# Sheet1.net
KiCad netlist of a schematic drawn in Altium Designer
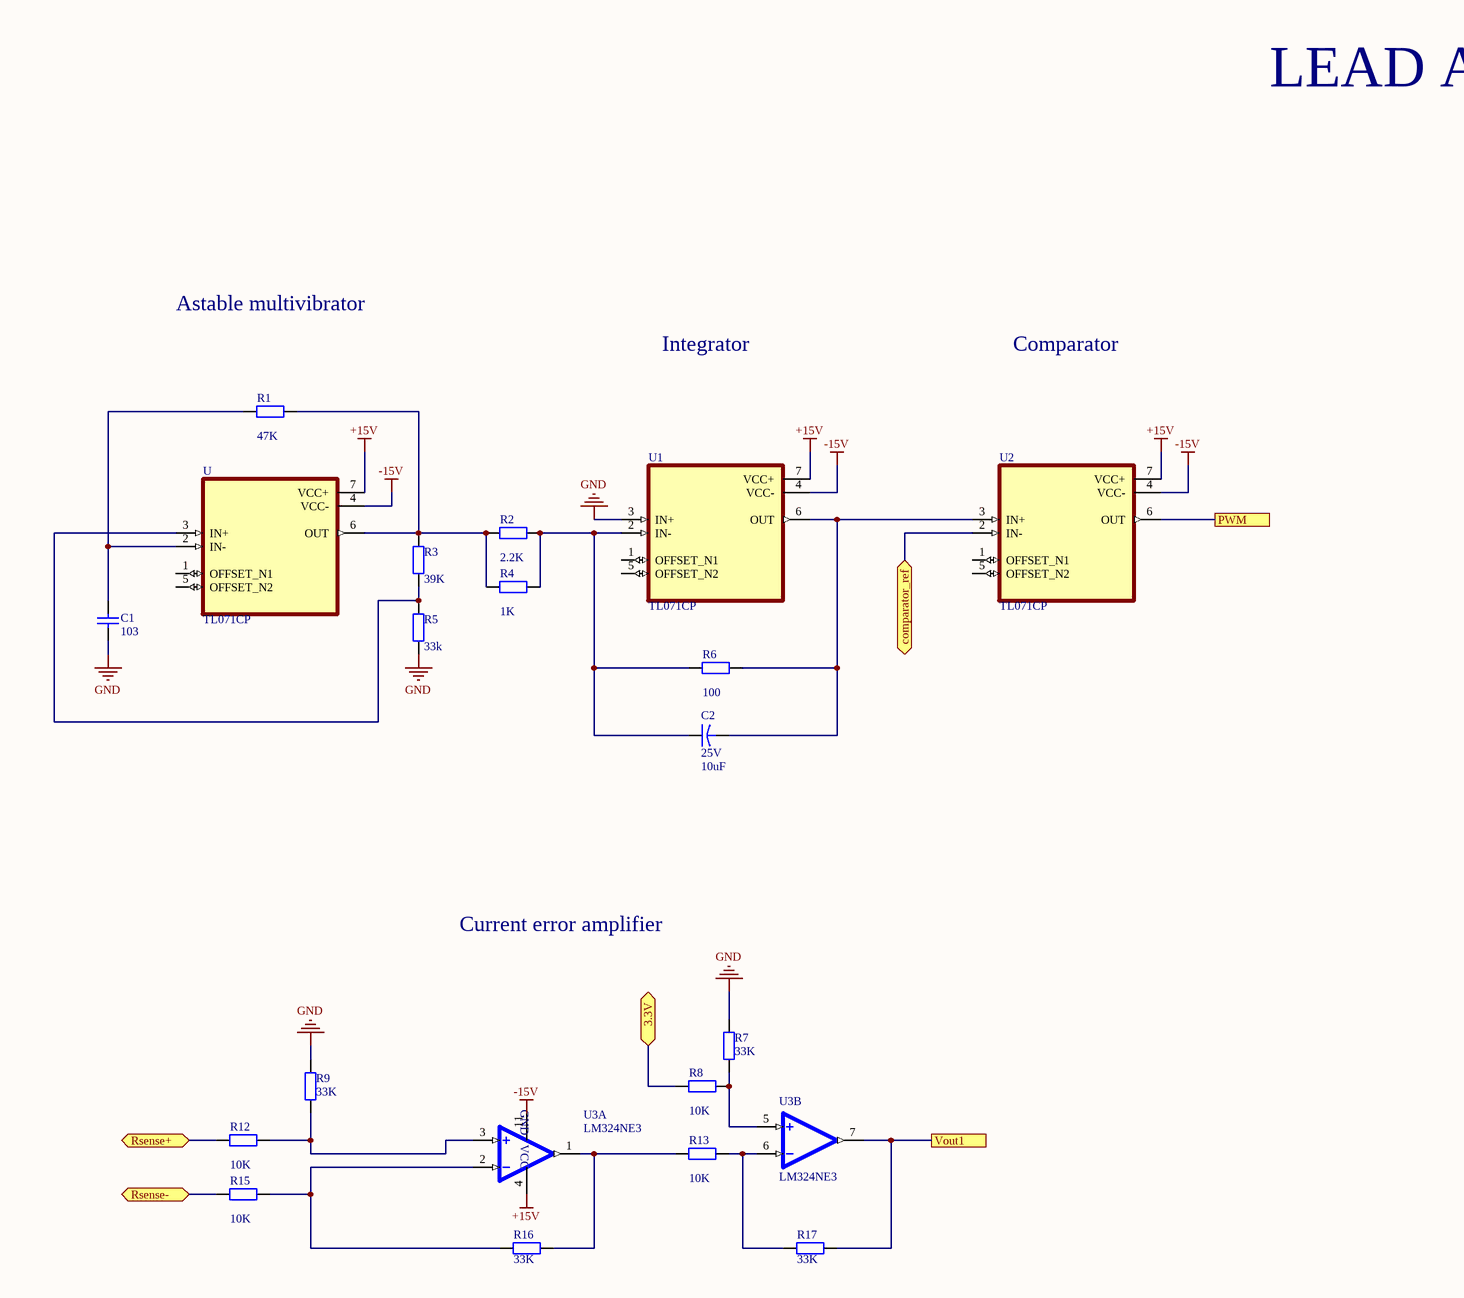
[diagram p0: Sheet1.SchDoc, top left]
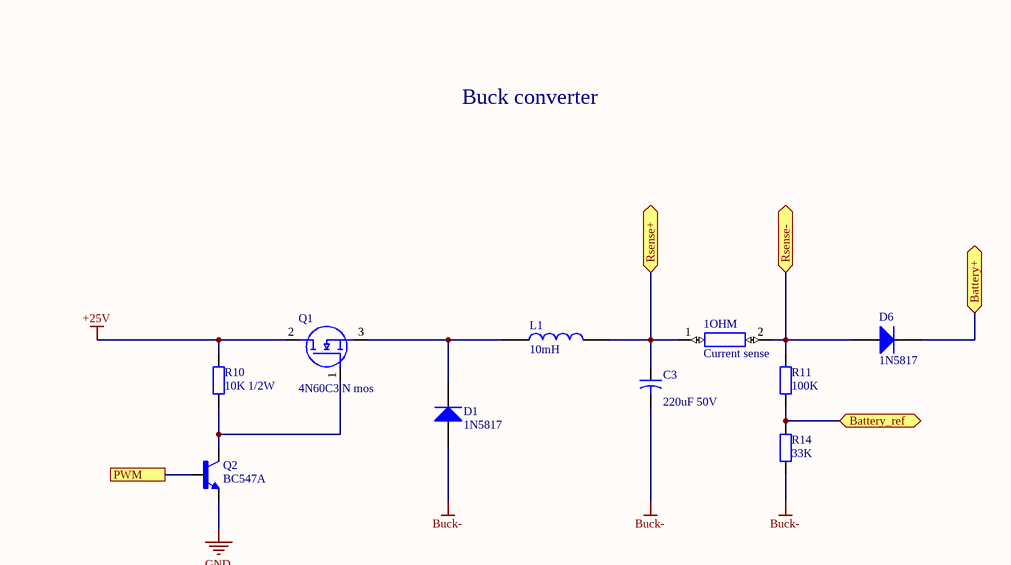
[diagram p1: Sheet1.SchDoc, top right]
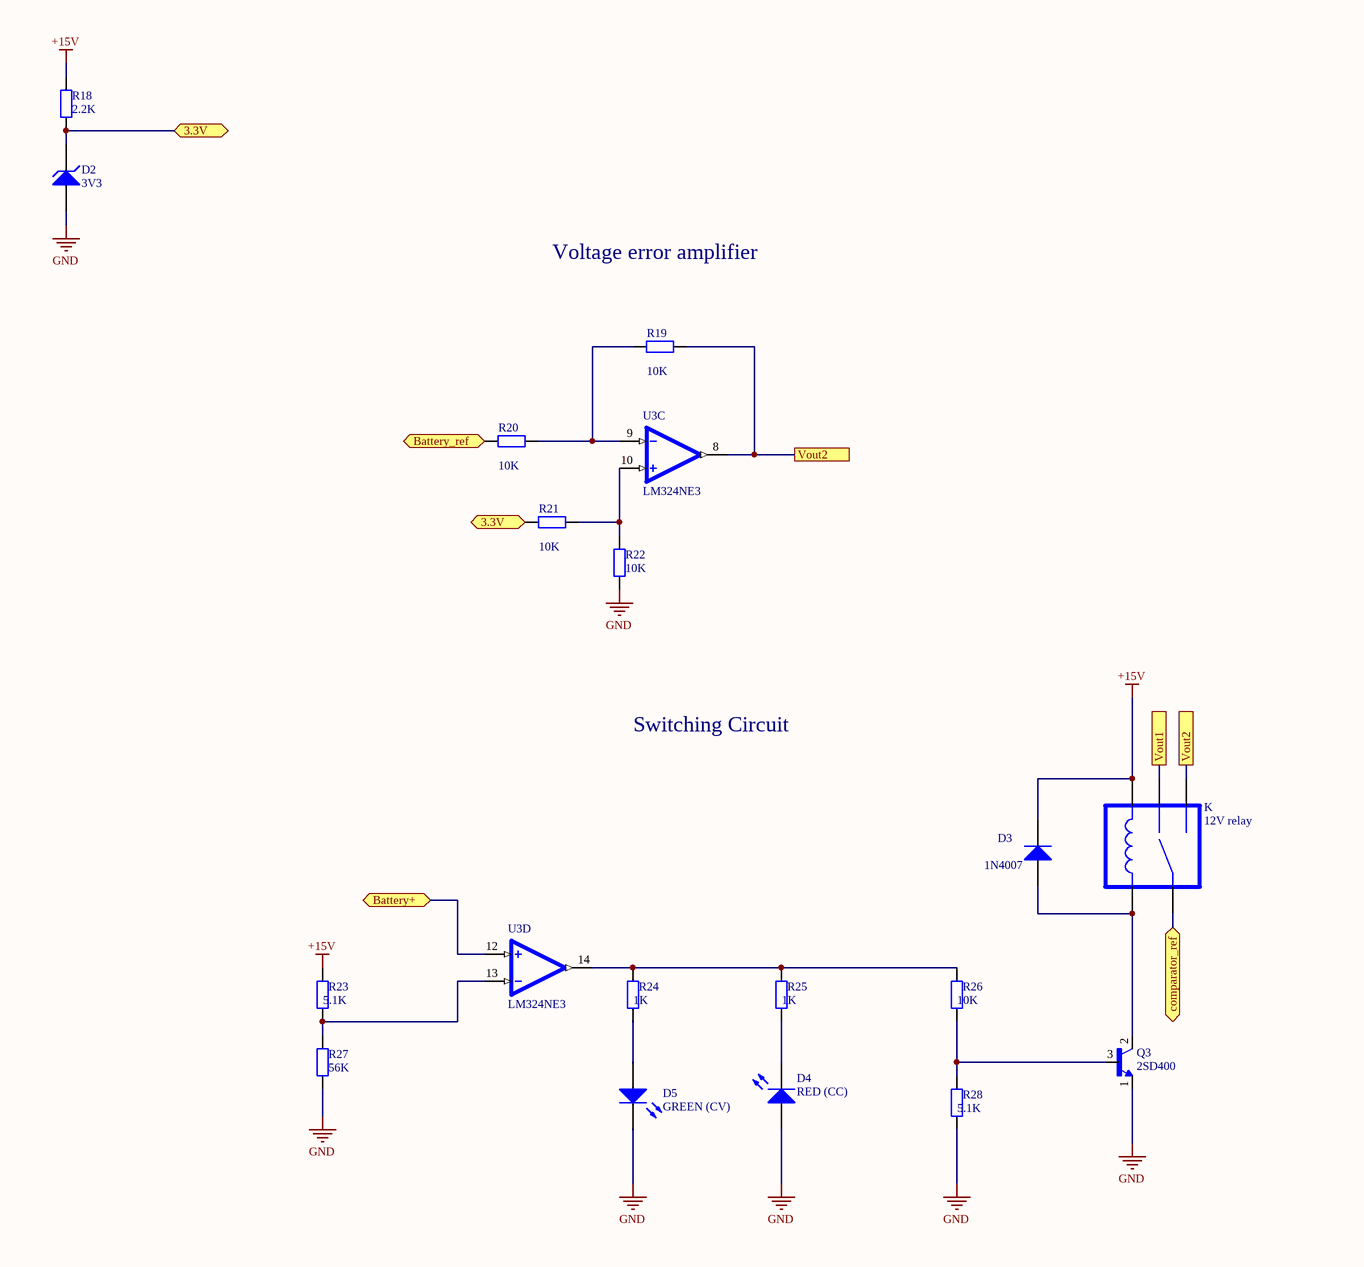
[diagram p2: Sheet1.SchDoc, bottom left]

(export (version "E")
  (design (tool "Eeschema 10.0.6"))
  (components
    (comp (ref "1OHM")
      (value "Current sense")
      (footprint "RESAD5860W102L2380D870")
      (description "25 kOhms Â±1% 5W Through Hole Resistor Axial Wirewound")
      (fields (field (name "MF") "Ohmite") (field (name "MP") "45F25KE"))
      (libsource (lib "45F25KE") (part "45F25KE"))
    )
    (comp (ref "C1")
      (value "103")
      (footprint "RAD-0.3")
      (description "Capacitor")
      (fields (field (name "PUBLISHER") "Altium Limited"))
      (libsource (lib "Miscellaneous Devices") (part "Cap"))
    )
    (comp (ref "C2")
      (value "25V")
      (footprint "CAPR5-4X5")
      (description "Capacitor")
      (fields (field (name "ALTIUM_VALUE") "10uF") (field (name "PUBLISHER") "Altium Limited"))
      (libsource (lib "Miscellaneous Devices") (part "Cap2"))
    )
    (comp (ref "C3")
      (value "220uF 50V")
      (footprint "CAPR5-4X5")
      (description "Capacitor")
      (fields (field (name "Comment") "Cap2") (field (name "PUBLISHER") "Altium Limited"))
      (libsource (lib "Miscellaneous Devices") (part "Cap2"))
    )
    (comp (ref "D1")
      (value "1N5817")
      (footprint "DO-41")
      (description "1 Amp General Purpose Rectifier")
      (fields (field (name "PUBLISHER") "Altium Limited"))
      (libsource (lib "Miscellaneous Devices") (part "Diode 1N4007"))
    )
    (comp (ref "D2")
      (value "3V3")
      (footprint "DIODE-0.7")
      (description "Zener Diode")
      (fields (field (name "PUBLISHER") "Altium Limited"))
      (libsource (lib "Miscellaneous Devices") (part "D Zener"))
    )
    (comp (ref "D3")
      (value "1N4007")
      (footprint "DO-41")
      (description "1 Amp General Purpose Rectifier")
      (fields (field (name "PUBLISHER") "Altium Limited"))
      (libsource (lib "Miscellaneous Devices") (part "Diode 1N4007"))
    )
    (comp (ref "D4")
      (value "RED (CC)")
      (footprint "LED-1")
      (description "Typical RED GaAs LED")
      (fields (field (name "PUBLISHER") "Altium Limited"))
      (libsource (lib "Miscellaneous Devices") (part "LED1"))
    )
    (comp (ref "D5")
      (value "GREEN (CV)")
      (footprint "LED-1")
      (description "Typical RED GaAs LED")
      (fields (field (name "PUBLISHER") "Altium Limited"))
      (libsource (lib "Miscellaneous Devices") (part "LED1"))
    )
    (comp (ref "D6")
      (value "1N5817")
      (footprint "DO-41")
      (description "1 Amp General Purpose Rectifier")
      (fields (field (name "PUBLISHER") "Altium Limited"))
      (libsource (lib "Miscellaneous Devices") (part "Diode 1N4007"))
    )
    (comp (ref "K")
      (value "12V relay")
      (footprint "TE_1461069-5")
      (description "General Purpose Relay SPDT _1 Form C_ 12VDC Coil Through Hole")
      (fields (field (name "MP") "1461069-5") (field (name "MF") "TE Connectivity"))
      (libsource (lib "1461069-5") (part "1461069-5"))
    )
    (comp (ref "L1")
      (value "10mH")
      (footprint "PE92102KNL")
      (description "Pulse 100 uH +/-20% Leaded Inductor, 2.6A Idc, 100m Rdc")
      (fields
        (field (name "MANUFACTURER_PART_NUMBER") "PE-92102KNL")
        (field (name "MOUSER PART NUMBER") "673-PE-92102KNL")
      )
      (libsource (lib "PE-92102KNL") (part "PE-92102KNL"))
    )
    (comp (ref "Q1")
      (value "4N60C3 N mos")
      (footprint "TO544P516X1586X2557-3P")
      (description "Infineon SPW24N60C3 N-channel MOSFET Transistor, 24.3 A, 650 V, 3-Pin TO-247")
      (fields
        (field (name "MANUFACTURER_PART_NUMBER") "SPW24N60C3")
        (field (name "MOUSER PART NUMBER") "726-SPW24N60C3")
      )
      (libsource (lib "SPW24N60C3") (part "SPW24N60C3"))
    )
    (comp (ref "Q2")
      (value "BC547A")
      (footprint "TO92250P510H770-3")
      (description "Bipolar (BJT) Transistor NPN 45 V 100 mA 300MHz 625 mW Through Hole TO-92 (TO-226)")
      (fields (field (name "MF") "ON Semiconductor"))
      (libsource (lib "BC547A") (part "BC547A"))
    )
    (comp (ref "Q3")
      (value "2SD400")
      (footprint "TO92250P510H770-3:TO92250P510H770-3")
      (description "TO-92MOD Transistor (NPN). Low-Frequency Power Amp, Electronic Governor Applications.")
      (fields (field (name "MF") "LGE"))
      (libsource (lib "2SD400") (part "2SD400"))
    )
    (comp (ref "R1")
      (value "47K")
      (footprint "AXIAL-0.4")
      (description "Resistor")
      (fields (field (name "Comment") "Res2") (field (name "PUBLISHER") "Altium Limited"))
      (libsource (lib "") (part "Res2_1"))
    )
    (comp (ref "R2")
      (value "2.2K")
      (footprint "AXIAL-0.4")
      (description "Resistor")
      (fields (field (name "Comment") "Res2") (field (name "PUBLISHER") "Altium Limited"))
      (libsource (lib "") (part "Res2_1"))
    )
    (comp (ref "R3")
      (value "39K")
      (footprint "AXIAL-0.4")
      (description "Resistor")
      (fields (field (name "Comment") "Res2") (field (name "PUBLISHER") "Altium Limited"))
      (libsource (lib "") (part "Res2_2"))
    )
    (comp (ref "R4")
      (value "1K")
      (footprint "AXIAL-0.4")
      (description "Resistor")
      (fields (field (name "Comment") "Res2") (field (name "PUBLISHER") "Altium Limited"))
      (libsource (lib "") (part "Res2_1"))
    )
    (comp (ref "R5")
      (value "33k")
      (footprint "AXIAL-0.4")
      (description "Resistor")
      (fields (field (name "Comment") "Res2") (field (name "PUBLISHER") "Altium Limited"))
      (libsource (lib "") (part "Res2_2"))
    )
    (comp (ref "R6")
      (value "100")
      (footprint "AXIAL-0.4")
      (description "Resistor")
      (fields (field (name "Comment") "Res2") (field (name "PUBLISHER") "Altium Limited"))
      (libsource (lib "") (part "Res2_1"))
    )
    (comp (ref "R7")
      (value "33K")
      (footprint "AXIAL-0.4")
      (description "Resistor")
      (fields (field (name "Comment") "Res2") (field (name "PUBLISHER") "Altium Limited"))
      (libsource (lib "Miscellaneous Devices") (part "Res2"))
    )
    (comp (ref "R8")
      (value "10K")
      (footprint "AXIAL-0.4")
      (description "Resistor")
      (fields (field (name "Comment") "Res2") (field (name "PUBLISHER") "Altium Limited"))
      (libsource (lib "") (part "Res2_1"))
    )
    (comp (ref "R9")
      (value "33K")
      (footprint "AXIAL-0.4")
      (description "Resistor")
      (fields (field (name "Comment") "Res2") (field (name "PUBLISHER") "Altium Limited"))
      (libsource (lib "") (part "Res2_2"))
    )
    (comp (ref "R10")
      (value "10K 1/2W")
      (footprint "AXIAL-0.4")
      (description "Resistor")
      (fields (field (name "Comment") "Res2") (field (name "PUBLISHER") "Altium Limited"))
      (libsource (lib "Miscellaneous Devices") (part "Res2"))
    )
    (comp (ref "R11")
      (value "100K")
      (footprint "AXIAL-0.4")
      (description "Resistor")
      (fields (field (name "Comment") "Res2") (field (name "PUBLISHER") "Altium Limited"))
      (libsource (lib "Miscellaneous Devices") (part "Res2"))
    )
    (comp (ref "R12")
      (value "10K")
      (footprint "AXIAL-0.4")
      (description "Resistor")
      (fields (field (name "Comment") "Res2") (field (name "PUBLISHER") "Altium Limited"))
      (libsource (lib "") (part "Res2_1"))
    )
    (comp (ref "R13")
      (value "10K")
      (footprint "AXIAL-0.4")
      (description "Resistor")
      (fields (field (name "Comment") "Res2") (field (name "PUBLISHER") "Altium Limited"))
      (libsource (lib "") (part "Res2_1"))
    )
    (comp (ref "R14")
      (value "33K")
      (footprint "AXIAL-0.4")
      (description "Resistor")
      (fields (field (name "Comment") "Res2") (field (name "PUBLISHER") "Altium Limited"))
      (libsource (lib "Miscellaneous Devices") (part "Res2"))
    )
    (comp (ref "R15")
      (value "10K")
      (footprint "AXIAL-0.4")
      (description "Resistor")
      (fields (field (name "Comment") "Res2") (field (name "PUBLISHER") "Altium Limited"))
      (libsource (lib "") (part "Res2_1"))
    )
    (comp (ref "R16")
      (value "33K")
      (footprint "AXIAL-0.4")
      (description "Resistor")
      (fields (field (name "Comment") "Res2") (field (name "PUBLISHER") "Altium Limited"))
      (libsource (lib "") (part "Res2_3"))
    )
    (comp (ref "R17")
      (value "33K")
      (footprint "AXIAL-0.4")
      (description "Resistor")
      (fields (field (name "Comment") "Res2") (field (name "PUBLISHER") "Altium Limited"))
      (libsource (lib "") (part "Res2_3"))
    )
    (comp (ref "R18")
      (value "2.2K")
      (footprint "AXIAL-0.4")
      (description "Resistor")
      (fields (field (name "Comment") "Res2") (field (name "PUBLISHER") "Altium Limited"))
      (libsource (lib "") (part "Res2_2"))
    )
    (comp (ref "R19")
      (value "10K")
      (footprint "AXIAL-0.4")
      (description "Resistor")
      (fields (field (name "Comment") "Res2") (field (name "PUBLISHER") "Altium Limited"))
      (libsource (lib "") (part "Res2_1"))
    )
    (comp (ref "R20")
      (value "10K")
      (footprint "AXIAL-0.4")
      (description "Resistor")
      (fields (field (name "Comment") "Res2") (field (name "PUBLISHER") "Altium Limited"))
      (libsource (lib "") (part "Res2_1"))
    )
    (comp (ref "R21")
      (value "10K")
      (footprint "AXIAL-0.4")
      (description "Resistor")
      (fields (field (name "Comment") "Res2") (field (name "PUBLISHER") "Altium Limited"))
      (libsource (lib "") (part "Res2_1"))
    )
    (comp (ref "R22")
      (value "10K")
      (footprint "AXIAL-0.4")
      (description "Resistor")
      (fields (field (name "Comment") "Res2") (field (name "PUBLISHER") "Altium Limited"))
      (libsource (lib "") (part "Res2_2"))
    )
    (comp (ref "R23")
      (value "5.1K")
      (footprint "AXIAL-0.4")
      (description "Resistor")
      (fields (field (name "Comment") "Res2") (field (name "PUBLISHER") "Altium Limited"))
      (libsource (lib "") (part "Res2_2"))
    )
    (comp (ref "R24")
      (value "1K")
      (footprint "AXIAL-0.4")
      (description "Resistor")
      (fields (field (name "Comment") "Res2") (field (name "PUBLISHER") "Altium Limited"))
      (libsource (lib "") (part "Res2_2"))
    )
    (comp (ref "R25")
      (value "1K")
      (footprint "AXIAL-0.4")
      (description "Resistor")
      (fields (field (name "Comment") "Res2") (field (name "PUBLISHER") "Altium Limited"))
      (libsource (lib "") (part "Res2_2"))
    )
    (comp (ref "R26")
      (value "10K")
      (footprint "AXIAL-0.4")
      (description "Resistor")
      (fields (field (name "Comment") "Res2") (field (name "PUBLISHER") "Altium Limited"))
      (libsource (lib "") (part "Res2_2"))
    )
    (comp (ref "R27")
      (value "56K")
      (footprint "AXIAL-0.4")
      (description "Resistor")
      (fields (field (name "Comment") "Res2") (field (name "PUBLISHER") "Altium Limited"))
      (libsource (lib "") (part "Res2_2"))
    )
    (comp (ref "R28")
      (value "5.1K")
      (footprint "AXIAL-0.4")
      (description "Resistor")
      (fields (field (name "Comment") "Res2") (field (name "PUBLISHER") "Altium Limited"))
      (libsource (lib "") (part "Res2_2"))
    )
    (comp (ref "U")
      (value "TL071CP")
      (footprint "DIP794W45P254L959H508Q8")
      (description "Low-Noise JFET-Input General-Purpose Operational Amplifier 8-PDIP 0 to 70")
      (fields (field (name "MF") "Texas Instruments"))
      (libsource (lib "TL071CP") (part "TL071CP"))
    )
    (comp (ref "U1")
      (value "TL071CP")
      (footprint "DIP794W45P254L959H508Q8")
      (description "Low-Noise JFET-Input General-Purpose Operational Amplifier 8-PDIP 0 to 70")
      (fields (field (name "MF") "Texas Instruments"))
      (libsource (lib "TL071CP") (part "TL071CP"))
    )
    (comp (ref "U2")
      (value "TL071CP")
      (footprint "DIP794W45P254L959H508Q8")
      (description "Low-Noise JFET-Input General-Purpose Operational Amplifier 8-PDIP 0 to 70")
      (fields (field (name "MF") "Texas Instruments"))
      (libsource (lib "TL071CP") (part "TL071CP"))
    )
    (comp (ref "U3")
      (value "LM324NE3")
      (footprint "DIP794W45P254L1969H508Q14")
      (description "Quad, 30-V, 1.2-MHz operational amplifier")
      (fields (field (name "MF") "Texas Instruments"))
      (libsource (lib "LM324NE3") (part "LM324NE3"))
    )
  )
  (nets
    (net (code "1") (name "+15V") (class "Default")
      (node (ref "D3") (pin "2") (pinfunction "K_2") (pintype "passive"))
      (node (ref "K") (pin "5") (pinfunction "M2_5") (pintype "passive"))
      (node (ref "R18") (pin "2") (pinfunction "2_2") (pintype "passive"))
      (node (ref "R23") (pin "2") (pinfunction "2_2") (pintype "passive"))
      (node (ref "U") (pin "7") (pinfunction "VCC+_7") (pintype "power_in"))
      (node (ref "U1") (pin "7") (pinfunction "VCC+_7") (pintype "power_in"))
      (node (ref "U2") (pin "7") (pinfunction "VCC+_7") (pintype "power_in"))
      (node (ref "U3") (pin "4") (pinfunction "VCC_4") (pintype "power_in"))
    )
    (net (code "2") (name "+25V") (class "Default")
      (node (ref "Q1") (pin "2") (pinfunction "D_2") (pintype "passive"))
      (node (ref "R10") (pin "1") (pinfunction "1_1") (pintype "passive"))
    )
    (net (code "3") (name "-15V") (class "Default")
      (node (ref "U") (pin "4") (pinfunction "VCC-_4") (pintype "power_in"))
      (node (ref "U1") (pin "4") (pinfunction "VCC-_4") (pintype "power_in"))
      (node (ref "U2") (pin "4") (pinfunction "VCC-_4") (pintype "power_in"))
      (node (ref "U3") (pin "11") (pinfunction "GND_11") (pintype "power_in"))
    )
    (net (code "4") (name "/3.3V") (class "Default")
      (node (ref "D2") (pin "2") (pinfunction "K_2") (pintype "passive"))
      (node (ref "R18") (pin "1") (pinfunction "1_1") (pintype "passive"))
      (node (ref "R21") (pin "1") (pinfunction "1_1") (pintype "passive"))
      (node (ref "R8") (pin "1") (pinfunction "1_1") (pintype "passive"))
    )
    (net (code "5") (name "/Battery+") (class "Default")
      (node (ref "D6") (pin "2") (pinfunction "K_2") (pintype "passive"))
      (node (ref "U3") (pin "12") (pinfunction "4IN+_12") (pintype "input"))
    )
    (net (code "6") (name "/Battery_ref") (class "Default")
      (node (ref "R11") (pin "2") (pinfunction "2_2") (pintype "passive"))
      (node (ref "R14") (pin "1") (pinfunction "1_1") (pintype "passive"))
      (node (ref "R20") (pin "1") (pinfunction "1_1") (pintype "passive"))
    )
    (net (code "7") (name "/PWM") (class "Default")
      (node (ref "Q2") (pin "2") (pinfunction "B_2") (pintype "passive"))
      (node (ref "U2") (pin "6") (pinfunction "OUT_6") (pintype "output"))
    )
    (net (code "8") (name "/Rsense+") (class "Default")
      (node (ref "1OHM") (pin "1") (pinfunction "1_1") (pintype "bidirectional"))
      (node (ref "C3") (pin "1") (pinfunction "1_1") (pintype "passive"))
      (node (ref "L1") (pin "2") (pinfunction "2_2") (pintype "passive"))
      (node (ref "R12") (pin "1") (pinfunction "1_1") (pintype "passive"))
    )
    (net (code "9") (name "/Rsense-") (class "Default")
      (node (ref "1OHM") (pin "2") (pinfunction "2_2") (pintype "bidirectional"))
      (node (ref "D6") (pin "1") (pinfunction "A_1") (pintype "passive"))
      (node (ref "R11") (pin "1") (pinfunction "1_1") (pintype "passive"))
      (node (ref "R15") (pin "1") (pinfunction "1_1") (pintype "passive"))
    )
    (net (code "10") (name "/Vout1") (class "Default")
      (node (ref "K") (pin "4") (pinfunction "NC_4") (pintype "passive"))
      (node (ref "R17") (pin "1") (pinfunction "1_1") (pintype "passive"))
      (node (ref "U3") (pin "7") (pinfunction "2OUT_7") (pintype "output"))
    )
    (net (code "11") (name "/Vout2") (class "Default")
      (node (ref "K") (pin "3") (pinfunction "NO_3") (pintype "passive"))
      (node (ref "R19") (pin "2") (pinfunction "2_2") (pintype "passive"))
      (node (ref "U3") (pin "8") (pinfunction "3OUT_8") (pintype "output"))
    )
    (net (code "12") (name "/comparator_ref") (class "Default")
      (node (ref "K") (pin "1") (pinfunction "C_1") (pintype "passive"))
      (node (ref "U2") (pin "2") (pinfunction "IN-_2") (pintype "input"))
    )
    (net (code "13") (name "Buck-") (class "Default")
      (node (ref "C3") (pin "2") (pinfunction "2_2") (pintype "passive"))
      (node (ref "D1") (pin "1") (pinfunction "A_1") (pintype "passive"))
      (node (ref "R14") (pin "2") (pinfunction "2_2") (pintype "passive"))
    )
    (net (code "14") (name "GND") (class "Default")
      (node (ref "C1") (pin "1") (pinfunction "1_1") (pintype "passive"))
      (node (ref "D2") (pin "1") (pinfunction "A_1") (pintype "passive"))
      (node (ref "D4") (pin "1") (pinfunction "A_1") (pintype "passive"))
      (node (ref "D5") (pin "2") (pinfunction "K_2") (pintype "passive"))
      (node (ref "Q2") (pin "3") (pinfunction "E_3") (pintype "passive"))
      (node (ref "Q3") (pin "1") (pinfunction "E_1") (pintype "passive"))
      (node (ref "R22") (pin "1") (pinfunction "1_1") (pintype "passive"))
      (node (ref "R27") (pin "1") (pinfunction "1_1") (pintype "passive"))
      (node (ref "R28") (pin "1") (pinfunction "1_1") (pintype "passive"))
      (node (ref "R5") (pin "1") (pinfunction "1_1") (pintype "passive"))
      (node (ref "R7") (pin "1") (pinfunction "1_1") (pintype "passive"))
      (node (ref "R9") (pin "2") (pinfunction "2_2") (pintype "passive"))
      (node (ref "U1") (pin "3") (pinfunction "IN+_3") (pintype "input"))
    )
    (net (code "15") (name "Net-(D1-K)") (class "Default")
      (node (ref "D1") (pin "2") (pinfunction "K_2") (pintype "passive"))
      (node (ref "L1") (pin "1") (pinfunction "1_1") (pintype "passive"))
      (node (ref "Q1") (pin "3") (pinfunction "S_3") (pintype "passive"))
    )
    (net (code "16") (name "Net-(D3-A)") (class "Default")
      (node (ref "D3") (pin "1") (pinfunction "A_1") (pintype "passive"))
      (node (ref "K") (pin "2") (pinfunction "M1_2") (pintype "passive"))
      (node (ref "Q3") (pin "2") (pinfunction "C_2") (pintype "passive"))
    )
    (net (code "17") (name "Net-(D4-K)") (class "Default")
      (node (ref "D4") (pin "2") (pinfunction "K_2") (pintype "passive"))
      (node (ref "R25") (pin "1") (pinfunction "1_1") (pintype "passive"))
    )
    (net (code "18") (name "Net-(D5-A)") (class "Default")
      (node (ref "D5") (pin "1") (pinfunction "A_1") (pintype "passive"))
      (node (ref "R24") (pin "1") (pinfunction "1_1") (pintype "passive"))
    )
    (net (code "19") (name "Net-(Q1-G)") (class "Default")
      (node (ref "Q1") (pin "1") (pinfunction "G_1") (pintype "passive"))
      (node (ref "Q2") (pin "1") (pinfunction "C_1") (pintype "passive"))
      (node (ref "R10") (pin "2") (pinfunction "2_2") (pintype "passive"))
    )
    (net (code "20") (name "Net-(Q3-B)") (class "Default")
      (node (ref "Q3") (pin "3") (pinfunction "B_3") (pintype "passive"))
      (node (ref "R26") (pin "1") (pinfunction "1_1") (pintype "passive"))
      (node (ref "R28") (pin "2") (pinfunction "2_2") (pintype "passive"))
    )
    (net (code "21") (name "Net-(U-IN+)") (class "Default")
      (node (ref "R3") (pin "1") (pinfunction "1_1") (pintype "passive"))
      (node (ref "R5") (pin "2") (pinfunction "2_2") (pintype "passive"))
      (node (ref "U") (pin "3") (pinfunction "IN+_3") (pintype "input"))
    )
    (net (code "22") (name "Net-(U-IN-)") (class "Default")
      (node (ref "C1") (pin "2") (pinfunction "2_2") (pintype "passive"))
      (node (ref "R1") (pin "1") (pinfunction "1_1") (pintype "passive"))
      (node (ref "U") (pin "2") (pinfunction "IN-_2") (pintype "input"))
    )
    (net (code "23") (name "Net-(U-OUT)") (class "Default")
      (node (ref "R1") (pin "2") (pinfunction "2_2") (pintype "passive"))
      (node (ref "R2") (pin "1") (pinfunction "1_1") (pintype "passive"))
      (node (ref "R3") (pin "2") (pinfunction "2_2") (pintype "passive"))
      (node (ref "R4") (pin "1") (pinfunction "1_1") (pintype "passive"))
      (node (ref "U") (pin "6") (pinfunction "OUT_6") (pintype "output"))
    )
    (net (code "24") (name "Net-(U1-IN-)") (class "Default")
      (node (ref "C2") (pin "1") (pinfunction "1_1") (pintype "passive"))
      (node (ref "R2") (pin "2") (pinfunction "2_2") (pintype "passive"))
      (node (ref "R4") (pin "2") (pinfunction "2_2") (pintype "passive"))
      (node (ref "R6") (pin "1") (pinfunction "1_1") (pintype "passive"))
      (node (ref "U1") (pin "2") (pinfunction "IN-_2") (pintype "input"))
    )
    (net (code "25") (name "Net-(U1-OUT)") (class "Default")
      (node (ref "C2") (pin "2") (pinfunction "2_2") (pintype "passive"))
      (node (ref "R6") (pin "2") (pinfunction "2_2") (pintype "passive"))
      (node (ref "U1") (pin "6") (pinfunction "OUT_6") (pintype "output"))
      (node (ref "U2") (pin "3") (pinfunction "IN+_3") (pintype "input"))
    )
    (net (code "26") (name "Net-(U3A-1IN+)") (class "Default")
      (node (ref "R12") (pin "2") (pinfunction "2_2") (pintype "passive"))
      (node (ref "R9") (pin "1") (pinfunction "1_1") (pintype "passive"))
      (node (ref "U3") (pin "3") (pinfunction "1IN+_3") (pintype "input"))
    )
    (net (code "27") (name "Net-(U3A-1IN-)") (class "Default")
      (node (ref "R15") (pin "2") (pinfunction "2_2") (pintype "passive"))
      (node (ref "R16") (pin "2") (pinfunction "2_2") (pintype "passive"))
      (node (ref "U3") (pin "2") (pinfunction "1IN-_2") (pintype "input"))
    )
    (net (code "28") (name "Net-(U3A-1OUT)") (class "Default")
      (node (ref "R13") (pin "1") (pinfunction "1_1") (pintype "passive"))
      (node (ref "R16") (pin "1") (pinfunction "1_1") (pintype "passive"))
      (node (ref "U3") (pin "1") (pinfunction "1OUT_1") (pintype "output"))
    )
    (net (code "29") (name "Net-(U3B-2IN+)") (class "Default")
      (node (ref "R7") (pin "2") (pinfunction "2_2") (pintype "passive"))
      (node (ref "R8") (pin "2") (pinfunction "2_2") (pintype "passive"))
      (node (ref "U3") (pin "5") (pinfunction "2IN+_5") (pintype "input"))
    )
    (net (code "30") (name "Net-(U3B-2IN-)") (class "Default")
      (node (ref "R13") (pin "2") (pinfunction "2_2") (pintype "passive"))
      (node (ref "R17") (pin "2") (pinfunction "2_2") (pintype "passive"))
      (node (ref "U3") (pin "6") (pinfunction "2IN-_6") (pintype "input"))
    )
    (net (code "31") (name "Net-(U3C-3IN+)") (class "Default")
      (node (ref "R21") (pin "2") (pinfunction "2_2") (pintype "passive"))
      (node (ref "R22") (pin "2") (pinfunction "2_2") (pintype "passive"))
      (node (ref "U3") (pin "10") (pinfunction "3IN+_10") (pintype "input"))
    )
    (net (code "32") (name "Net-(U3C-3IN-)") (class "Default")
      (node (ref "R19") (pin "1") (pinfunction "1_1") (pintype "passive"))
      (node (ref "R20") (pin "2") (pinfunction "2_2") (pintype "passive"))
      (node (ref "U3") (pin "9") (pinfunction "3IN-_9") (pintype "input"))
    )
    (net (code "33") (name "Net-(U3D-4IN-)") (class "Default")
      (node (ref "R23") (pin "1") (pinfunction "1_1") (pintype "passive"))
      (node (ref "R27") (pin "2") (pinfunction "2_2") (pintype "passive"))
      (node (ref "U3") (pin "13") (pinfunction "4IN-_13") (pintype "input"))
    )
    (net (code "34") (name "Net-(U3D-4OUT)") (class "Default")
      (node (ref "R24") (pin "2") (pinfunction "2_2") (pintype "passive"))
      (node (ref "R25") (pin "2") (pinfunction "2_2") (pintype "passive"))
      (node (ref "R26") (pin "2") (pinfunction "2_2") (pintype "passive"))
      (node (ref "U3") (pin "14") (pinfunction "4OUT_14") (pintype "output"))
    )
    (net (code "35") (name "unconnected-(U-OFFSET_N1-Pad1)") (class "Default")
      (node (ref "U") (pin "1") (pinfunction "OFFSET_N1_1") (pintype "bidirectional"))
    )
    (net (code "36") (name "unconnected-(U-OFFSET_N2-Pad5)") (class "Default")
      (node (ref "U") (pin "5") (pinfunction "OFFSET_N2_5") (pintype "bidirectional"))
    )
    (net (code "37") (name "unconnected-(U1-OFFSET_N1-Pad1)") (class "Default")
      (node (ref "U1") (pin "1") (pinfunction "OFFSET_N1_1") (pintype "bidirectional"))
    )
    (net (code "38") (name "unconnected-(U1-OFFSET_N2-Pad5)") (class "Default")
      (node (ref "U1") (pin "5") (pinfunction "OFFSET_N2_5") (pintype "bidirectional"))
    )
    (net (code "39") (name "unconnected-(U2-OFFSET_N1-Pad1)") (class "Default")
      (node (ref "U2") (pin "1") (pinfunction "OFFSET_N1_1") (pintype "bidirectional"))
    )
    (net (code "40") (name "unconnected-(U2-OFFSET_N2-Pad5)") (class "Default")
      (node (ref "U2") (pin "5") (pinfunction "OFFSET_N2_5") (pintype "bidirectional"))
    )
  )
)
